# Controller.net
KiCad netlist of a schematic drawn in EAGLE
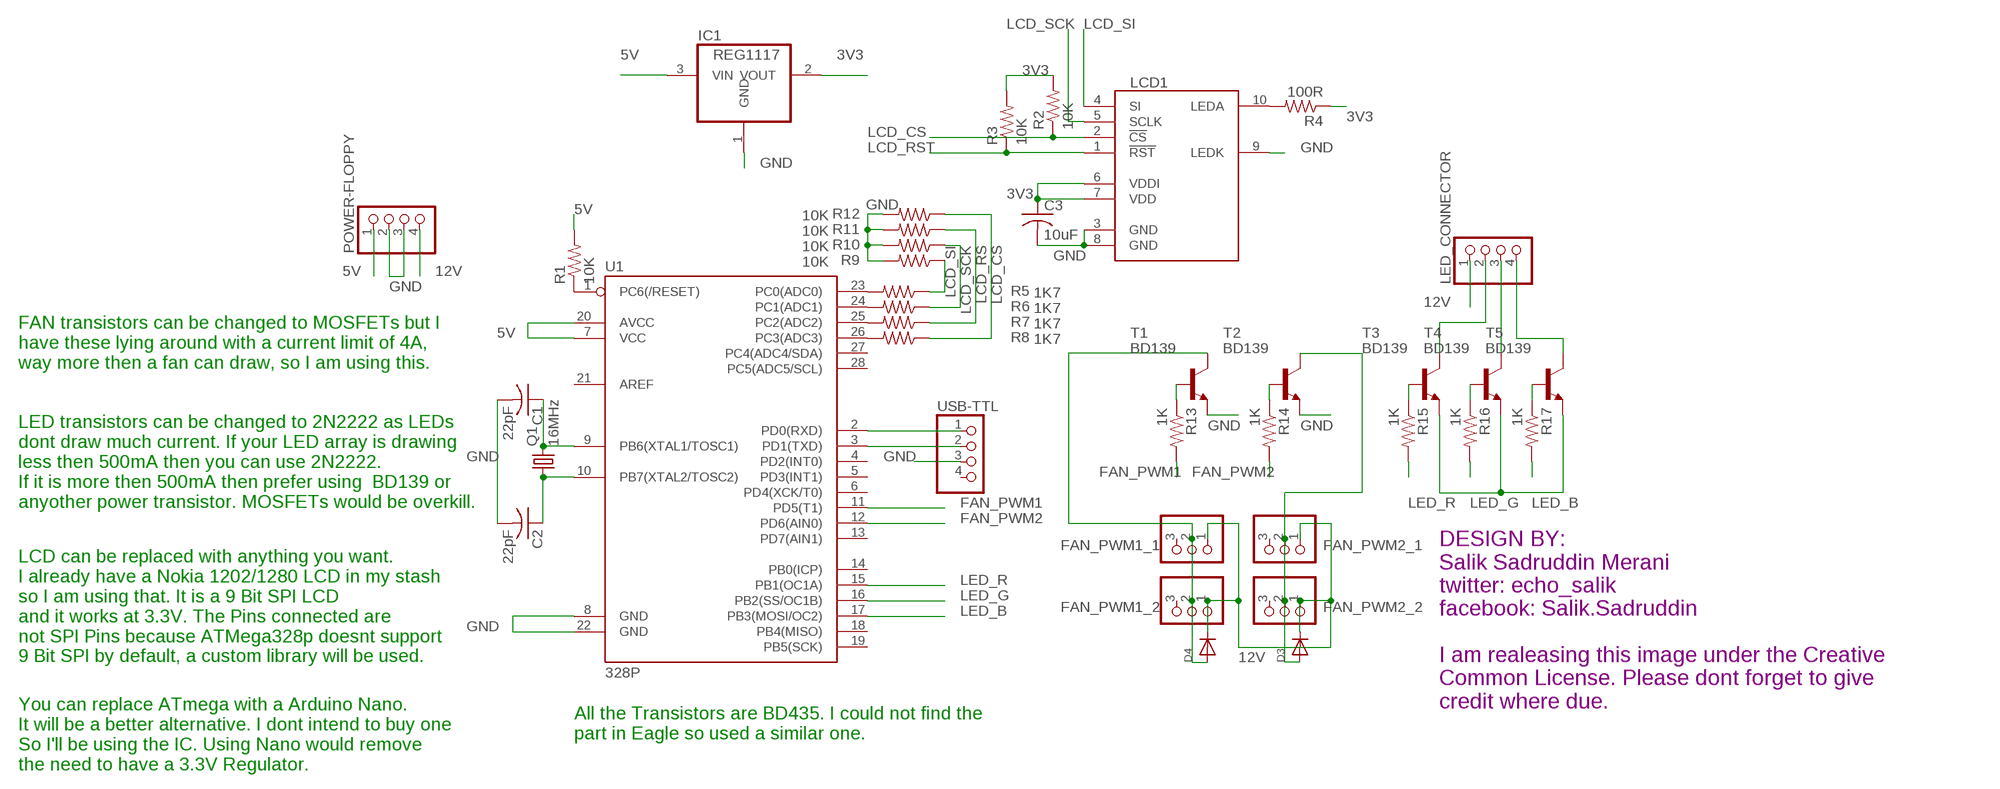
[diagram p0: schematic, sheet 1]

(export (version "E")
  (design (tool "Eeschema 10.0.6"))
  (components
    (comp (ref "C1")
      (value "22pF")
      (footprint "eagle-import:C050-025X075")
      (libsource (lib "eagle-import") (part "C-US050-025X075"))
    )
    (comp (ref "C2")
      (value "22pF")
      (footprint "eagle-import:C050-025X075")
      (libsource (lib "eagle-import") (part "C-US050-025X075"))
    )
    (comp (ref "C3")
      (value "10uF")
      (footprint "eagle-import:C050-025X075")
      (libsource (lib "eagle-import") (part "C-US050-025X075"))
    )
    (comp (ref "D3")
      (value "DIODEDO-1N4148")
      (footprint "eagle-import:DO-1N4148")
      (libsource (lib "eagle-import") (part "DIODEDO-1N4148"))
    )
    (comp (ref "D4")
      (value "DIODEDO-1N4148")
      (footprint "eagle-import:DO-1N4148")
      (libsource (lib "eagle-import") (part "DIODEDO-1N4148"))
    )
    (comp (ref "FAN_PWM1_1")
      (value "PINHD-1X3")
      (footprint "eagle-import:1X03")
      (libsource (lib "eagle-import") (part "PINHD-1X3"))
    )
    (comp (ref "FAN_PWM1_2")
      (value "PINHD-1X3")
      (footprint "eagle-import:1X03")
      (libsource (lib "eagle-import") (part "PINHD-1X3"))
    )
    (comp (ref "FAN_PWM2_1")
      (value "PINHD-1X3")
      (footprint "eagle-import:1X03")
      (libsource (lib "eagle-import") (part "PINHD-1X3"))
    )
    (comp (ref "FAN_PWM2_2")
      (value "PINHD-1X3")
      (footprint "eagle-import:1X03")
      (libsource (lib "eagle-import") (part "PINHD-1X3"))
    )
    (comp (ref "IC1")
      (value "REG1117")
      (footprint "eagle-import:SOT223")
      (libsource (lib "eagle-import") (part "REG1117"))
    )
    (comp (ref "LCD1")
      (value "LCD1202")
      (footprint "eagle-import:NOKIA1202LCD")
      (libsource (lib "eagle-import") (part "LCD1202"))
    )
    (comp (ref "LED_CONNECTOR")
      (value "PINHD-1X4")
      (footprint "eagle-import:1X04")
      (libsource (lib "eagle-import") (part "PINHD-1X4"))
    )
    (comp (ref "POWER-FLOPPY")
      (value "PINHD-1X4")
      (footprint "eagle-import:1X04")
      (libsource (lib "eagle-import") (part "PINHD-1X4"))
    )
    (comp (ref "Q1")
      (value "16MHz")
      (footprint "eagle-import:HC49_S")
      (libsource (lib "eagle-import") (part "CRYSTALHC49S"))
    )
    (comp (ref "R1")
      (value "10K")
      (footprint "eagle-import:0207_10")
      (libsource (lib "eagle-import") (part "R-US_0207/10"))
    )
    (comp (ref "R2")
      (value "10K")
      (footprint "eagle-import:0207_10")
      (libsource (lib "eagle-import") (part "R-US_0207/10"))
    )
    (comp (ref "R3")
      (value "10K")
      (footprint "eagle-import:0207_10")
      (libsource (lib "eagle-import") (part "R-US_0207/10"))
    )
    (comp (ref "R4")
      (value "100R")
      (footprint "eagle-import:0207_10")
      (libsource (lib "eagle-import") (part "R-US_0207/10"))
    )
    (comp (ref "R5")
      (value "1K7")
      (footprint "eagle-import:0207_10")
      (libsource (lib "eagle-import") (part "R-US_0207/10"))
    )
    (comp (ref "R6")
      (value "1K7")
      (footprint "eagle-import:0207_10")
      (libsource (lib "eagle-import") (part "R-US_0207/10"))
    )
    (comp (ref "R7")
      (value "1K7")
      (footprint "eagle-import:0207_10")
      (libsource (lib "eagle-import") (part "R-US_0207/10"))
    )
    (comp (ref "R8")
      (value "1K7")
      (footprint "eagle-import:0207_10")
      (libsource (lib "eagle-import") (part "R-US_0207/10"))
    )
    (comp (ref "R9")
      (value "10K")
      (footprint "eagle-import:0207_10")
      (libsource (lib "eagle-import") (part "R-US_0207/10"))
    )
    (comp (ref "R10")
      (value "10K")
      (footprint "eagle-import:0207_10")
      (libsource (lib "eagle-import") (part "R-US_0207/10"))
    )
    (comp (ref "R11")
      (value "10K")
      (footprint "eagle-import:0207_10")
      (libsource (lib "eagle-import") (part "R-US_0207/10"))
    )
    (comp (ref "R12")
      (value "10K")
      (footprint "eagle-import:0207_10")
      (libsource (lib "eagle-import") (part "R-US_0207/10"))
    )
    (comp (ref "R13")
      (value "1K")
      (footprint "eagle-import:0207_10")
      (libsource (lib "eagle-import") (part "R-US_0207/10"))
    )
    (comp (ref "R14")
      (value "1K")
      (footprint "eagle-import:0207_10")
      (libsource (lib "eagle-import") (part "R-US_0207/10"))
    )
    (comp (ref "R15")
      (value "1K")
      (footprint "eagle-import:0207_10")
      (libsource (lib "eagle-import") (part "R-US_0207/10"))
    )
    (comp (ref "R16")
      (value "1K")
      (footprint "eagle-import:0207_10")
      (libsource (lib "eagle-import") (part "R-US_0207/10"))
    )
    (comp (ref "R17")
      (value "1K")
      (footprint "eagle-import:0207_10")
      (libsource (lib "eagle-import") (part "R-US_0207/10"))
    )
    (comp (ref "T1")
      (value "BD139")
      (footprint "eagle-import:TO126")
      (libsource (lib "eagle-import") (part "BD139"))
    )
    (comp (ref "T2")
      (value "BD139")
      (footprint "eagle-import:TO126")
      (libsource (lib "eagle-import") (part "BD139"))
    )
    (comp (ref "T3")
      (value "BD139")
      (footprint "eagle-import:TO126")
      (libsource (lib "eagle-import") (part "BD139"))
    )
    (comp (ref "T4")
      (value "BD139")
      (footprint "eagle-import:TO126")
      (libsource (lib "eagle-import") (part "BD139"))
    )
    (comp (ref "T5")
      (value "BD139")
      (footprint "eagle-import:TO126")
      (libsource (lib "eagle-import") (part "BD139"))
    )
    (comp (ref "U1")
      (value "328P")
      (footprint "eagle-import:DIP28")
      (libsource (lib "eagle-import") (part "ATMEGA328P_PDIP"))
    )
    (comp (ref "USB-TTL")
      (value "PINHD-1X4")
      (footprint "eagle-import:1X04")
      (libsource (lib "eagle-import") (part "PINHD-1X4"))
    )
  )
  (nets
    (net (code "1") (name "/3V3") (class "Default")
      (node (ref "C3") (pin "1") (pinfunction "1_1") (pintype "passive"))
      (node (ref "IC1") (pin "2") (pinfunction "VOUT_2") (pintype "output"))
      (node (ref "LCD1") (pin "6") (pinfunction "VDDI_6") (pintype "power_in"))
      (node (ref "LCD1") (pin "7") (pinfunction "VDD_7") (pintype "power_in"))
      (node (ref "R2") (pin "2") (pinfunction "2_2") (pintype "passive"))
      (node (ref "R3") (pin "2") (pinfunction "2_2") (pintype "passive"))
      (node (ref "R4") (pin "1") (pinfunction "1_1") (pintype "passive"))
    )
    (net (code "2") (name "/5V") (class "Default")
      (node (ref "IC1") (pin "3") (pinfunction "VIN_3") (pintype "input"))
      (node (ref "POWER-FLOPPY") (pin "1") (pinfunction "1_1") (pintype "passive"))
      (node (ref "R1") (pin "2") (pinfunction "2_2") (pintype "passive"))
      (node (ref "U1") (pin "20") (pinfunction "AVCC_20") (pintype "bidirectional"))
      (node (ref "U1") (pin "7") (pinfunction "VCC_7") (pintype "bidirectional"))
    )
    (net (code "3") (name "/12V") (class "Default")
      (node (ref "D3") (pin "C") (pinfunction "C_C") (pintype "passive"))
      (node (ref "D4") (pin "C") (pinfunction "C_C") (pintype "passive"))
      (node (ref "FAN_PWM1_1") (pin "1") (pinfunction "1_1") (pintype "passive"))
      (node (ref "FAN_PWM1_2") (pin "1") (pinfunction "1_1") (pintype "passive"))
      (node (ref "FAN_PWM2_1") (pin "1") (pinfunction "1_1") (pintype "passive"))
      (node (ref "FAN_PWM2_2") (pin "1") (pinfunction "1_1") (pintype "passive"))
      (node (ref "LED_CONNECTOR") (pin "1") (pinfunction "1_1") (pintype "passive"))
      (node (ref "POWER-FLOPPY") (pin "4") (pinfunction "4_4") (pintype "passive"))
    )
    (net (code "4") (name "/FAN_PWM1") (class "Default")
      (node (ref "R13") (pin "2") (pinfunction "2_2") (pintype "passive"))
      (node (ref "U1") (pin "11") (pinfunction "PD5(T1)_11") (pintype "bidirectional"))
    )
    (net (code "5") (name "/FAN_PWM2") (class "Default")
      (node (ref "R14") (pin "2") (pinfunction "2_2") (pintype "passive"))
      (node (ref "U1") (pin "12") (pinfunction "PD6(AIN0)_12") (pintype "bidirectional"))
    )
    (net (code "6") (name "/GND") (class "Default")
      (node (ref "C1") (pin "2") (pinfunction "2_2") (pintype "passive"))
      (node (ref "C2") (pin "2") (pinfunction "2_2") (pintype "passive"))
      (node (ref "C3") (pin "2") (pinfunction "2_2") (pintype "passive"))
      (node (ref "IC1") (pin "1") (pinfunction "GND_1") (pintype "power_in"))
      (node (ref "LCD1") (pin "3") (pinfunction "GND_3") (pintype "power_in"))
      (node (ref "LCD1") (pin "8") (pinfunction "GND_8") (pintype "power_in"))
      (node (ref "LCD1") (pin "9") (pinfunction "LEDK_9") (pintype "passive"))
      (node (ref "POWER-FLOPPY") (pin "2") (pinfunction "2_2") (pintype "passive"))
      (node (ref "POWER-FLOPPY") (pin "3") (pinfunction "3_3") (pintype "passive"))
      (node (ref "R10") (pin "2") (pinfunction "2_2") (pintype "passive"))
      (node (ref "R11") (pin "2") (pinfunction "2_2") (pintype "passive"))
      (node (ref "R12") (pin "2") (pinfunction "2_2") (pintype "passive"))
      (node (ref "R9") (pin "2") (pinfunction "2_2") (pintype "passive"))
      (node (ref "T1") (pin "1") (pinfunction "E_1") (pintype "passive"))
      (node (ref "T2") (pin "1") (pinfunction "E_1") (pintype "passive"))
      (node (ref "U1") (pin "22") (pinfunction "GND_22") (pintype "bidirectional"))
      (node (ref "U1") (pin "8") (pinfunction "GND_8") (pintype "bidirectional"))
      (node (ref "USB-TTL") (pin "3") (pinfunction "3_3") (pintype "passive"))
    )
    (net (code "7") (name "/LCD_CS") (class "Default")
      (node (ref "LCD1") (pin "2") (pinfunction "~{CS}_2") (pintype "input"))
      (node (ref "R12") (pin "1") (pinfunction "1_1") (pintype "passive"))
      (node (ref "R2") (pin "1") (pinfunction "1_1") (pintype "passive"))
      (node (ref "R8") (pin "1") (pinfunction "1_1") (pintype "passive"))
    )
    (net (code "8") (name "/LCD_RS") (class "Default")
      (node (ref "R11") (pin "1") (pinfunction "1_1") (pintype "passive"))
      (node (ref "R7") (pin "1") (pinfunction "1_1") (pintype "passive"))
    )
    (net (code "9") (name "/LCD_RST") (class "Default")
      (node (ref "LCD1") (pin "1") (pinfunction "~{RST}_1") (pintype "input"))
      (node (ref "R3") (pin "1") (pinfunction "1_1") (pintype "passive"))
    )
    (net (code "10") (name "/LCD_SCK") (class "Default")
      (node (ref "LCD1") (pin "5") (pinfunction "SCLK_5") (pintype "input"))
      (node (ref "R10") (pin "1") (pinfunction "1_1") (pintype "passive"))
      (node (ref "R6") (pin "1") (pinfunction "1_1") (pintype "passive"))
    )
    (net (code "11") (name "/LCD_SI") (class "Default")
      (node (ref "LCD1") (pin "4") (pinfunction "SI_4") (pintype "input"))
      (node (ref "R5") (pin "1") (pinfunction "1_1") (pintype "passive"))
      (node (ref "R9") (pin "1") (pinfunction "1_1") (pintype "passive"))
    )
    (net (code "12") (name "/LED_B") (class "Default")
      (node (ref "R17") (pin "2") (pinfunction "2_2") (pintype "passive"))
      (node (ref "U1") (pin "17") (pinfunction "PB3(MOSI/OC2)_17") (pintype "bidirectional"))
    )
    (net (code "13") (name "/LED_G") (class "Default")
      (node (ref "R16") (pin "2") (pinfunction "2_2") (pintype "passive"))
      (node (ref "U1") (pin "16") (pinfunction "PB2(SS/OC1B)_16") (pintype "bidirectional"))
    )
    (net (code "14") (name "/LED_R") (class "Default")
      (node (ref "R15") (pin "2") (pinfunction "2_2") (pintype "passive"))
      (node (ref "U1") (pin "15") (pinfunction "PB1(OC1A)_15") (pintype "bidirectional"))
    )
    (net (code "15") (name "Net-(LCD1-LEDA)") (class "Default")
      (node (ref "LCD1") (pin "10") (pinfunction "LEDA_10") (pintype "passive"))
      (node (ref "R4") (pin "2") (pinfunction "2_2") (pintype "passive"))
    )
    (net (code "16") (name "Net-(T1-B)") (class "Default")
      (node (ref "R13") (pin "1") (pinfunction "1_1") (pintype "passive"))
      (node (ref "T1") (pin "3") (pinfunction "B_3") (pintype "passive"))
    )
    (net (code "17") (name "Net-(T1-C)") (class "Default")
      (node (ref "D4") (pin "A") (pinfunction "A_A") (pintype "passive"))
      (node (ref "FAN_PWM1_1") (pin "2") (pinfunction "2_2") (pintype "passive"))
      (node (ref "FAN_PWM1_2") (pin "2") (pinfunction "2_2") (pintype "passive"))
      (node (ref "T1") (pin "2") (pinfunction "C_2") (pintype "passive"))
    )
    (net (code "18") (name "Net-(T2-B)") (class "Default")
      (node (ref "R14") (pin "1") (pinfunction "1_1") (pintype "passive"))
      (node (ref "T2") (pin "3") (pinfunction "B_3") (pintype "passive"))
    )
    (net (code "19") (name "Net-(T2-C)") (class "Default")
      (node (ref "D3") (pin "A") (pinfunction "A_A") (pintype "passive"))
      (node (ref "FAN_PWM2_1") (pin "2") (pinfunction "2_2") (pintype "passive"))
      (node (ref "FAN_PWM2_2") (pin "2") (pinfunction "2_2") (pintype "passive"))
      (node (ref "T2") (pin "2") (pinfunction "C_2") (pintype "passive"))
    )
    (net (code "20") (name "Net-(T3-B)") (class "Default")
      (node (ref "R15") (pin "1") (pinfunction "1_1") (pintype "passive"))
      (node (ref "T3") (pin "3") (pinfunction "B_3") (pintype "passive"))
    )
    (net (code "21") (name "Net-(T3-C)") (class "Default")
      (node (ref "LED_CONNECTOR") (pin "2") (pinfunction "2_2") (pintype "passive"))
      (node (ref "T3") (pin "2") (pinfunction "C_2") (pintype "passive"))
    )
    (net (code "22") (name "Net-(T3-E)") (class "Default")
      (node (ref "T3") (pin "1") (pinfunction "E_1") (pintype "passive"))
      (node (ref "T4") (pin "1") (pinfunction "E_1") (pintype "passive"))
      (node (ref "T5") (pin "1") (pinfunction "E_1") (pintype "passive"))
    )
    (net (code "23") (name "Net-(T4-B)") (class "Default")
      (node (ref "R16") (pin "1") (pinfunction "1_1") (pintype "passive"))
      (node (ref "T4") (pin "3") (pinfunction "B_3") (pintype "passive"))
    )
    (net (code "24") (name "Net-(T4-C)") (class "Default")
      (node (ref "LED_CONNECTOR") (pin "3") (pinfunction "3_3") (pintype "passive"))
      (node (ref "T4") (pin "2") (pinfunction "C_2") (pintype "passive"))
    )
    (net (code "25") (name "Net-(T5-B)") (class "Default")
      (node (ref "R17") (pin "1") (pinfunction "1_1") (pintype "passive"))
      (node (ref "T5") (pin "3") (pinfunction "B_3") (pintype "passive"))
    )
    (net (code "26") (name "Net-(T5-C)") (class "Default")
      (node (ref "LED_CONNECTOR") (pin "4") (pinfunction "4_4") (pintype "passive"))
      (node (ref "T5") (pin "2") (pinfunction "C_2") (pintype "passive"))
    )
    (net (code "27") (name "Net-(U1-PB6(XTAL1{slash}TOSC1))") (class "Default")
      (node (ref "C1") (pin "1") (pinfunction "1_1") (pintype "passive"))
      (node (ref "Q1") (pin "2") (pinfunction "2_2") (pintype "passive"))
      (node (ref "U1") (pin "9") (pinfunction "PB6(XTAL1/TOSC1)_9") (pintype "bidirectional"))
    )
    (net (code "28") (name "Net-(U1-PB7(XTAL2{slash}TOSC2))") (class "Default")
      (node (ref "C2") (pin "1") (pinfunction "1_1") (pintype "passive"))
      (node (ref "Q1") (pin "1") (pinfunction "1_1") (pintype "passive"))
      (node (ref "U1") (pin "10") (pinfunction "PB7(XTAL2/TOSC2)_10") (pintype "bidirectional"))
    )
    (net (code "29") (name "Net-(U1-PC0(ADC0))") (class "Default")
      (node (ref "R5") (pin "2") (pinfunction "2_2") (pintype "passive"))
      (node (ref "U1") (pin "23") (pinfunction "PC0(ADC0)_23") (pintype "bidirectional"))
    )
    (net (code "30") (name "Net-(U1-PC1(ADC1))") (class "Default")
      (node (ref "R6") (pin "2") (pinfunction "2_2") (pintype "passive"))
      (node (ref "U1") (pin "24") (pinfunction "PC1(ADC1)_24") (pintype "bidirectional"))
    )
    (net (code "31") (name "Net-(U1-PC2(ADC2))") (class "Default")
      (node (ref "R7") (pin "2") (pinfunction "2_2") (pintype "passive"))
      (node (ref "U1") (pin "25") (pinfunction "PC2(ADC2)_25") (pintype "bidirectional"))
    )
    (net (code "32") (name "Net-(U1-PC3(ADC3))") (class "Default")
      (node (ref "R8") (pin "2") (pinfunction "2_2") (pintype "passive"))
      (node (ref "U1") (pin "26") (pinfunction "PC3(ADC3)_26") (pintype "bidirectional"))
    )
    (net (code "33") (name "Net-(U1-PC6({slash}RESET))") (class "Default")
      (node (ref "R1") (pin "1") (pinfunction "1_1") (pintype "passive"))
      (node (ref "U1") (pin "1") (pinfunction "PC6(/RESET)_1") (pintype "bidirectional"))
    )
    (net (code "34") (name "Net-(U1-PD0(RXD))") (class "Default")
      (node (ref "U1") (pin "2") (pinfunction "PD0(RXD)_2") (pintype "bidirectional"))
      (node (ref "USB-TTL") (pin "1") (pinfunction "1_1") (pintype "passive"))
    )
    (net (code "35") (name "Net-(U1-PD1(TXD))") (class "Default")
      (node (ref "U1") (pin "3") (pinfunction "PD1(TXD)_3") (pintype "bidirectional"))
      (node (ref "USB-TTL") (pin "2") (pinfunction "2_2") (pintype "passive"))
    )
    (net (code "36") (name "unconnected-(FAN_PWM1_1-Pad3)") (class "Default")
      (node (ref "FAN_PWM1_1") (pin "3") (pinfunction "3_3") (pintype "passive"))
    )
    (net (code "37") (name "unconnected-(FAN_PWM1_2-Pad3)") (class "Default")
      (node (ref "FAN_PWM1_2") (pin "3") (pinfunction "3_3") (pintype "passive"))
    )
    (net (code "38") (name "unconnected-(FAN_PWM2_1-Pad3)") (class "Default")
      (node (ref "FAN_PWM2_1") (pin "3") (pinfunction "3_3") (pintype "passive"))
    )
    (net (code "39") (name "unconnected-(FAN_PWM2_2-Pad3)") (class "Default")
      (node (ref "FAN_PWM2_2") (pin "3") (pinfunction "3_3") (pintype "passive"))
    )
    (net (code "40") (name "unconnected-(U1-AREF-Pad21)") (class "Default")
      (node (ref "U1") (pin "21") (pinfunction "AREF_21") (pintype "bidirectional"))
    )
    (net (code "41") (name "unconnected-(U1-PB0(ICP)-Pad14)") (class "Default")
      (node (ref "U1") (pin "14") (pinfunction "PB0(ICP)_14") (pintype "bidirectional"))
    )
    (net (code "42") (name "unconnected-(U1-PB4(MISO)-Pad18)") (class "Default")
      (node (ref "U1") (pin "18") (pinfunction "PB4(MISO)_18") (pintype "bidirectional"))
    )
    (net (code "43") (name "unconnected-(U1-PB5(SCK)-Pad19)") (class "Default")
      (node (ref "U1") (pin "19") (pinfunction "PB5(SCK)_19") (pintype "bidirectional"))
    )
    (net (code "44") (name "unconnected-(U1-PC4(ADC4{slash}SDA)-Pad27)") (class "Default")
      (node (ref "U1") (pin "27") (pinfunction "PC4(ADC4/SDA)_27") (pintype "bidirectional"))
    )
    (net (code "45") (name "unconnected-(U1-PC5(ADC5{slash}SCL)-Pad28)") (class "Default")
      (node (ref "U1") (pin "28") (pinfunction "PC5(ADC5/SCL)_28") (pintype "bidirectional"))
    )
    (net (code "46") (name "unconnected-(U1-PD2(INT0)-Pad4)") (class "Default")
      (node (ref "U1") (pin "4") (pinfunction "PD2(INT0)_4") (pintype "bidirectional"))
    )
    (net (code "47") (name "unconnected-(U1-PD3(INT1)-Pad5)") (class "Default")
      (node (ref "U1") (pin "5") (pinfunction "PD3(INT1)_5") (pintype "bidirectional"))
    )
    (net (code "48") (name "unconnected-(U1-PD4(XCK{slash}T0)-Pad6)") (class "Default")
      (node (ref "U1") (pin "6") (pinfunction "PD4(XCK/T0)_6") (pintype "bidirectional"))
    )
    (net (code "49") (name "unconnected-(U1-PD7(AIN1)-Pad13)") (class "Default")
      (node (ref "U1") (pin "13") (pinfunction "PD7(AIN1)_13") (pintype "bidirectional"))
    )
    (net (code "50") (name "unconnected-(USB-TTL-Pad4)") (class "Default")
      (node (ref "USB-TTL") (pin "4") (pinfunction "4_4") (pintype "passive"))
    )
  )
)
